# pcb.net
KiCad netlist of a schematic drawn in EasyEDA Pro
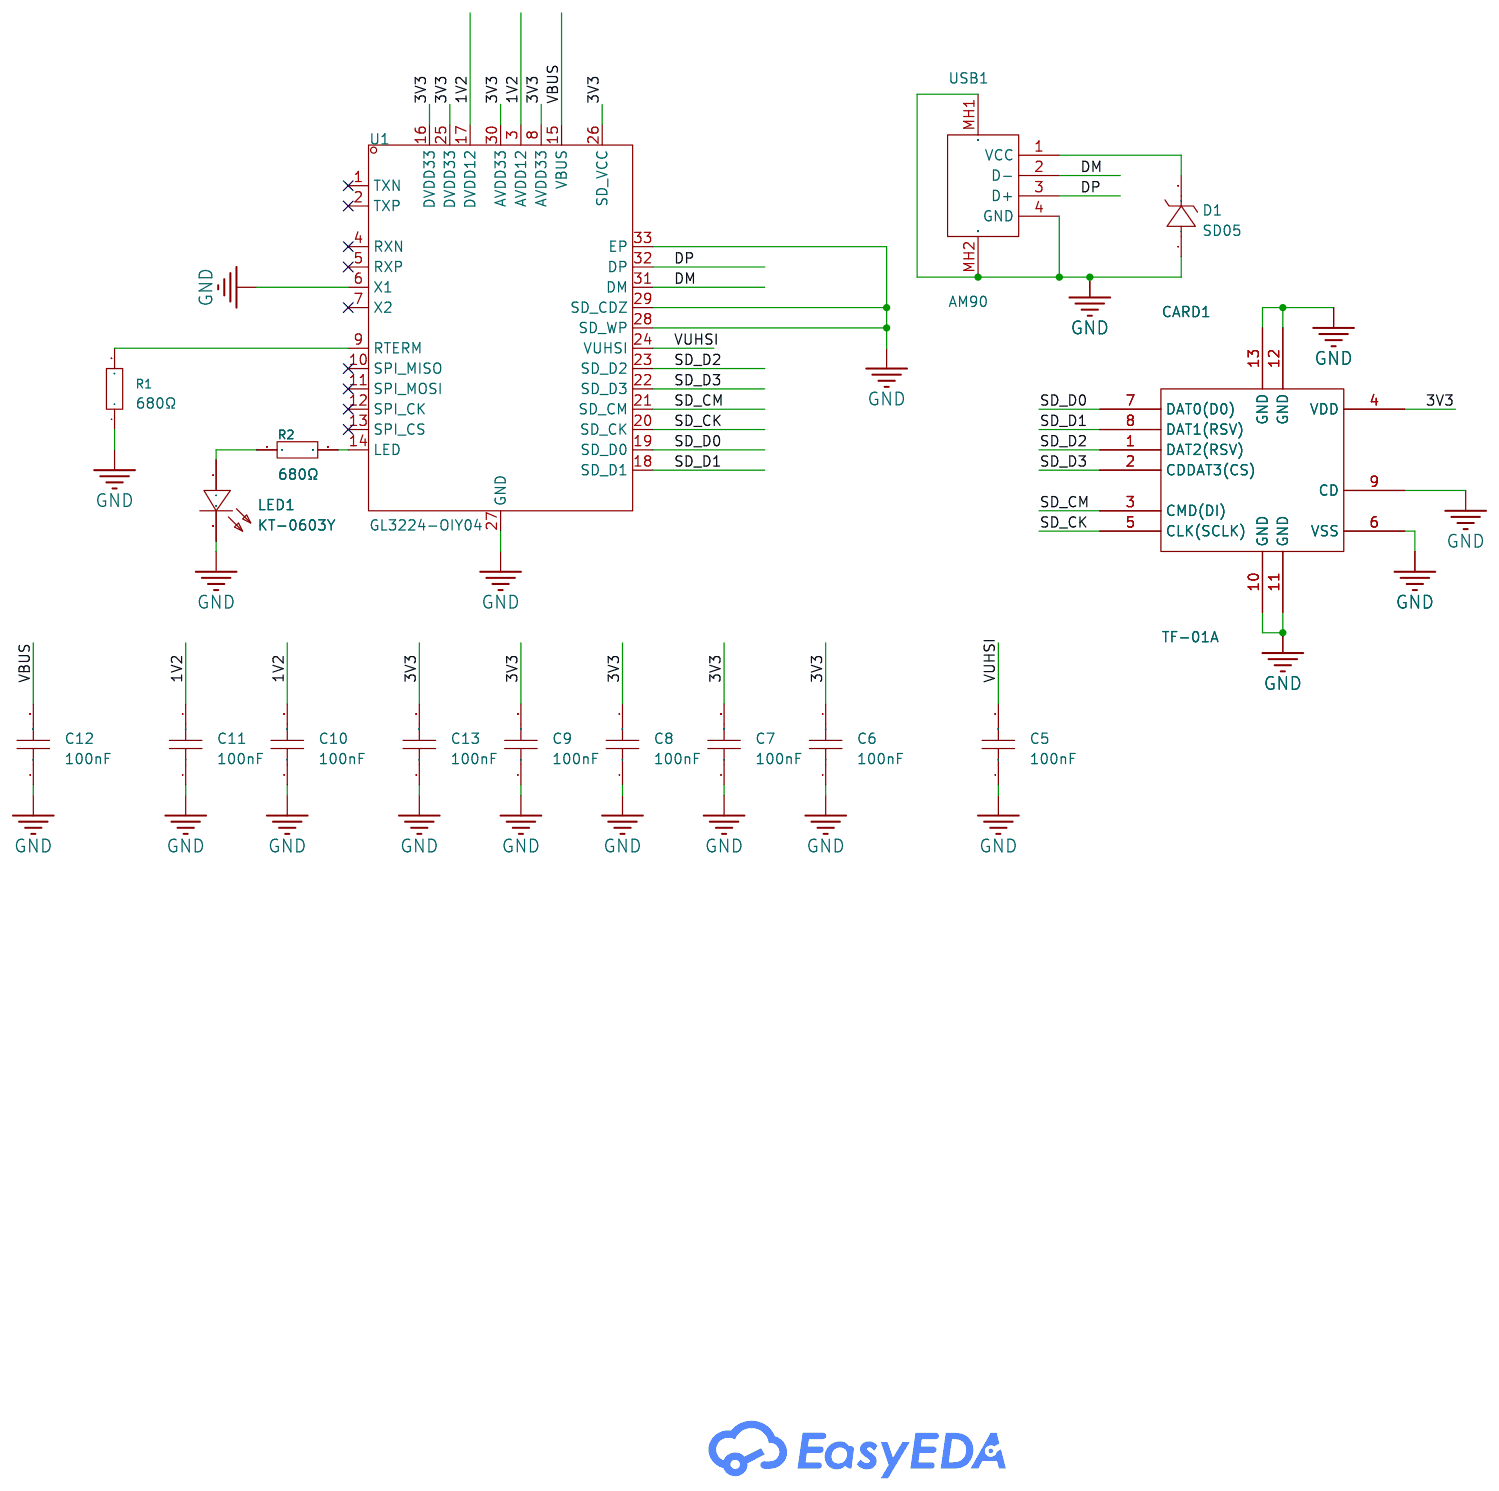
[diagram p0: schematic sheet]

(export (version "E")
  (design (tool "Eeschema 10.0.6"))
  (components
    (comp (ref "C5")
      (value "100nF")
      (footprint "easyedapro:C0402")
      (description "Capacitance:100nF Tolerance:±10% Tolerance:±10% Voltage Rating:16V Temperature Coefficient:X7R")
      (fields
        (field (name "Manufacturer Part") "CL05B104KO5NNNC")
        (field (name "Manufacturer") "SAMSUNG(三星)")
      )
      (libsource (lib "easyedapro") (part "CL05B104KO5NNNC"))
    )
    (comp (ref "C6")
      (value "100nF")
      (footprint "easyedapro:C0402")
      (description "Capacitance:100nF Tolerance:±10% Tolerance:±10% Voltage Rating:16V Temperature Coefficient:X7R")
      (fields
        (field (name "Manufacturer Part") "CL05B104KO5NNNC")
        (field (name "Manufacturer") "SAMSUNG(三星)")
      )
      (libsource (lib "easyedapro") (part "CL05B104KO5NNNC"))
    )
    (comp (ref "C7")
      (value "100nF")
      (footprint "easyedapro:C0402")
      (description "Capacitance:100nF Tolerance:±10% Tolerance:±10% Voltage Rating:16V Temperature Coefficient:X7R")
      (fields
        (field (name "Manufacturer Part") "CL05B104KO5NNNC")
        (field (name "Manufacturer") "SAMSUNG(三星)")
      )
      (libsource (lib "easyedapro") (part "CL05B104KO5NNNC"))
    )
    (comp (ref "C8")
      (value "100nF")
      (footprint "easyedapro:C0402")
      (description "Capacitance:100nF Tolerance:±10% Tolerance:±10% Voltage Rating:16V Temperature Coefficient:X7R")
      (fields
        (field (name "Manufacturer Part") "CL05B104KO5NNNC")
        (field (name "Manufacturer") "SAMSUNG(三星)")
      )
      (libsource (lib "easyedapro") (part "CL05B104KO5NNNC"))
    )
    (comp (ref "C9")
      (value "100nF")
      (footprint "easyedapro:C0402")
      (description "Capacitance:100nF Tolerance:±10% Tolerance:±10% Voltage Rating:16V Temperature Coefficient:X7R")
      (fields
        (field (name "Manufacturer Part") "CL05B104KO5NNNC")
        (field (name "Manufacturer") "SAMSUNG(三星)")
      )
      (libsource (lib "easyedapro") (part "CL05B104KO5NNNC"))
    )
    (comp (ref "C10")
      (value "100nF")
      (footprint "easyedapro:C0402")
      (description "Capacitance:100nF Tolerance:±10% Tolerance:±10% Voltage Rating:16V Temperature Coefficient:X7R")
      (fields
        (field (name "Manufacturer Part") "CL05B104KO5NNNC")
        (field (name "Manufacturer") "SAMSUNG(三星)")
      )
      (libsource (lib "easyedapro") (part "CL05B104KO5NNNC"))
    )
    (comp (ref "C11")
      (value "100nF")
      (footprint "easyedapro:C0402")
      (description "Capacitance:100nF Tolerance:±10% Tolerance:±10% Voltage Rating:16V Temperature Coefficient:X7R")
      (fields
        (field (name "Manufacturer Part") "CL05B104KO5NNNC")
        (field (name "Manufacturer") "SAMSUNG(三星)")
      )
      (libsource (lib "easyedapro") (part "CL05B104KO5NNNC"))
    )
    (comp (ref "C12")
      (value "100nF")
      (footprint "easyedapro:C0402")
      (description "Capacitance:100nF Tolerance:±10% Tolerance:±10% Voltage Rating:16V Temperature Coefficient:X7R")
      (fields
        (field (name "Manufacturer Part") "CL05B104KO5NNNC")
        (field (name "Manufacturer") "SAMSUNG(三星)")
      )
      (libsource (lib "easyedapro") (part "CL05B104KO5NNNC"))
    )
    (comp (ref "C13")
      (value "100nF")
      (footprint "easyedapro:C0402")
      (description "Capacitance:100nF Tolerance:±10% Tolerance:±10% Voltage Rating:16V Temperature Coefficient:X7R")
      (fields
        (field (name "Manufacturer Part") "CL05B104KO5NNNC")
        (field (name "Manufacturer") "SAMSUNG(三星)")
      )
      (libsource (lib "easyedapro") (part "CL05B104KO5NNNC"))
    )
    (comp (ref "CARD1")
      (value "TF-01A")
      (footprint "easyedapro:TF-SMD_TF-01A")
      (fields (field (name "Manufacturer") "韩国韩荣"))
      (libsource (lib "easyedapro") (part "TF-01A"))
    )
    (comp (ref "D1")
      (value "SD05")
      (footprint "easyedapro:SOD-323_L1.8-W1.3-LS2.5-FD")
      (fields (field (name "Manufacturer") "MDD(辰达半导体)"))
      (libsource (lib "easyedapro") (part "SD05_C502527"))
    )
    (comp (ref "LED1")
      (value "KT-0603Y")
      (footprint "easyedapro:LED0603-R-RD")
      (fields (field (name "Manufacturer") "KENTO"))
      (libsource (lib "easyedapro") (part "0603YYellow light 90-110"))
    )
    (comp (ref "R1")
      (value "680Ω")
      (footprint "easyedapro:R0603")
      (fields
        (field (name "Manufacturer Part") "0603WAF6800T5E")
        (field (name "Manufacturer") "UNI-ROYAL(厚声)")
      )
      (libsource (lib "easyedapro") (part "0603WAF6800T5E"))
    )
    (comp (ref "R2")
      (value "680Ω")
      (footprint "easyedapro:R0603")
      (fields
        (field (name "Manufacturer Part") "0603WAF6800T5E")
        (field (name "Manufacturer") "UNI-ROYAL(厚声)")
      )
      (libsource (lib "easyedapro") (part "0603WAF6800T5E"))
    )
    (comp (ref "U1")
      (value "GL3224-OIY04")
      (footprint "easyedapro:HQFN-32_L5.0-W5.0-P0.50-BL-EP3.0")
      (fields (field (name "Manufacturer") "GENESYS(创惟)"))
      (libsource (lib "easyedapro") (part "GL3224-OIY04"))
    )
    (comp (ref "USB1")
      (value "AM90")
      (footprint "easyedapro:USB-AM-TH_AM90")
      (fields (field (name "Manufacturer") "SHOU HAN(首韩)"))
      (libsource (lib "easyedapro") (part "AM90"))
    )
  )
  (nets
    (net (code "1") (name "/1V2") (class "Default")
      (node (ref "C10") (pin "2") (pinfunction "2_2") (pintype "unspecified"))
      (node (ref "C11") (pin "2") (pinfunction "2_2") (pintype "unspecified"))
      (node (ref "U1") (pin "17") (pinfunction "DVDD12_17") (pintype "unspecified"))
      (node (ref "U1") (pin "3") (pinfunction "AVDD12_3") (pintype "unspecified"))
    )
    (net (code "2") (name "/3V3") (class "Default")
      (node (ref "C13") (pin "2") (pinfunction "2_2") (pintype "unspecified"))
      (node (ref "C6") (pin "2") (pinfunction "2_2") (pintype "unspecified"))
      (node (ref "C7") (pin "2") (pinfunction "2_2") (pintype "unspecified"))
      (node (ref "C8") (pin "2") (pinfunction "2_2") (pintype "unspecified"))
      (node (ref "C9") (pin "2") (pinfunction "2_2") (pintype "unspecified"))
      (node (ref "CARD1") (pin "4") (pinfunction "VDD_4") (pintype "input"))
      (node (ref "U1") (pin "16") (pinfunction "DVDD33_16") (pintype "unspecified"))
      (node (ref "U1") (pin "25") (pinfunction "DVDD33_25") (pintype "unspecified"))
      (node (ref "U1") (pin "26") (pinfunction "SD_VCC_26") (pintype "unspecified"))
      (node (ref "U1") (pin "30") (pinfunction "AVDD33_30") (pintype "unspecified"))
      (node (ref "U1") (pin "8") (pinfunction "AVDD33_8") (pintype "unspecified"))
    )
    (net (code "3") (name "/DM") (class "Default")
      (node (ref "U1") (pin "31") (pinfunction "DM_31") (pintype "unspecified"))
      (node (ref "USB1") (pin "2") (pinfunction "D-_2") (pintype "input"))
    )
    (net (code "4") (name "/DP") (class "Default")
      (node (ref "U1") (pin "32") (pinfunction "DP_32") (pintype "unspecified"))
      (node (ref "USB1") (pin "3") (pinfunction "D+_3") (pintype "input"))
    )
    (net (code "5") (name "/SD_CK") (class "Default")
      (node (ref "CARD1") (pin "5") (pinfunction "CLK(SCLK)_5") (pintype "input"))
      (node (ref "U1") (pin "20") (pinfunction "SD_CK_20") (pintype "unspecified"))
    )
    (net (code "6") (name "/SD_CM") (class "Default")
      (node (ref "CARD1") (pin "3") (pinfunction "CMD(DI)_3") (pintype "input"))
      (node (ref "U1") (pin "21") (pinfunction "SD_CM_21") (pintype "unspecified"))
    )
    (net (code "7") (name "/SD_D0") (class "Default")
      (node (ref "CARD1") (pin "7") (pinfunction "DAT0(D0)_7") (pintype "bidirectional"))
      (node (ref "U1") (pin "19") (pinfunction "SD_D0_19") (pintype "unspecified"))
    )
    (net (code "8") (name "/SD_D1") (class "Default")
      (node (ref "CARD1") (pin "8") (pinfunction "DAT1(RSV)_8") (pintype "bidirectional"))
      (node (ref "U1") (pin "18") (pinfunction "SD_D1_18") (pintype "unspecified"))
    )
    (net (code "9") (name "/SD_D2") (class "Default")
      (node (ref "CARD1") (pin "1") (pinfunction "DAT2(RSV)_1") (pintype "bidirectional"))
      (node (ref "U1") (pin "23") (pinfunction "SD_D2_23") (pintype "unspecified"))
    )
    (net (code "10") (name "/SD_D3") (class "Default")
      (node (ref "CARD1") (pin "2") (pinfunction "CDDAT3(CS)_2") (pintype "bidirectional"))
      (node (ref "U1") (pin "22") (pinfunction "SD_D3_22") (pintype "unspecified"))
    )
    (net (code "11") (name "/VBUS") (class "Default")
      (node (ref "C12") (pin "2") (pinfunction "2_2") (pintype "unspecified"))
      (node (ref "U1") (pin "15") (pinfunction "VBUS_15") (pintype "unspecified"))
    )
    (net (code "12") (name "/VUHSI") (class "Default")
      (node (ref "C5") (pin "2") (pinfunction "2_2") (pintype "unspecified"))
      (node (ref "U1") (pin "24") (pinfunction "VUHSI_24") (pintype "unspecified"))
    )
    (net (code "13") (name "GND") (class "Default")
      (node (ref "C10") (pin "1") (pinfunction "1_1") (pintype "unspecified"))
      (node (ref "C11") (pin "1") (pinfunction "1_1") (pintype "unspecified"))
      (node (ref "C12") (pin "1") (pinfunction "1_1") (pintype "unspecified"))
      (node (ref "C13") (pin "1") (pinfunction "1_1") (pintype "unspecified"))
      (node (ref "C5") (pin "1") (pinfunction "1_1") (pintype "unspecified"))
      (node (ref "C6") (pin "1") (pinfunction "1_1") (pintype "unspecified"))
      (node (ref "C7") (pin "1") (pinfunction "1_1") (pintype "unspecified"))
      (node (ref "C8") (pin "1") (pinfunction "1_1") (pintype "unspecified"))
      (node (ref "C9") (pin "1") (pinfunction "1_1") (pintype "unspecified"))
      (node (ref "CARD1") (pin "10") (pinfunction "GND_10") (pintype "input"))
      (node (ref "CARD1") (pin "11") (pinfunction "GND_11") (pintype "input"))
      (node (ref "CARD1") (pin "12") (pinfunction "GND_12") (pintype "input"))
      (node (ref "CARD1") (pin "13") (pinfunction "GND_13") (pintype "input"))
      (node (ref "CARD1") (pin "6") (pinfunction "VSS_6") (pintype "input"))
      (node (ref "CARD1") (pin "9") (pinfunction "CD_9") (pintype "input"))
      (node (ref "D1") (pin "1") (pinfunction "A_1") (pintype "unspecified"))
      (node (ref "LED1") (pin "2") (pinfunction "K_2") (pintype "unspecified"))
      (node (ref "R1") (pin "1") (pinfunction "1_1") (pintype "input"))
      (node (ref "U1") (pin "27") (pinfunction "GND_27") (pintype "unspecified"))
      (node (ref "U1") (pin "28") (pinfunction "SD_WP_28") (pintype "unspecified"))
      (node (ref "U1") (pin "29") (pinfunction "SD_CDZ_29") (pintype "unspecified"))
      (node (ref "U1") (pin "33") (pinfunction "EP_33") (pintype "unspecified"))
      (node (ref "U1") (pin "6") (pinfunction "X1_6") (pintype "unspecified"))
      (node (ref "USB1") (pin "4") (pinfunction "GND_4") (pintype "input"))
      (node (ref "USB1") (pin "MH1") (pinfunction "MH1_MH1") (pintype "unspecified"))
      (node (ref "USB1") (pin "MH2") (pinfunction "MH2_MH2") (pintype "unspecified"))
    )
    (net (code "14") (name "Net-(D1-K)") (class "Default")
      (node (ref "D1") (pin "2") (pinfunction "K_2") (pintype "unspecified"))
      (node (ref "USB1") (pin "1") (pinfunction "VCC_1") (pintype "input"))
    )
    (net (code "15") (name "Net-(LED1-A)") (class "Default")
      (node (ref "LED1") (pin "1") (pinfunction "A_1") (pintype "unspecified"))
      (node (ref "R2") (pin "1") (pinfunction "1_1") (pintype "input"))
    )
    (net (code "16") (name "Net-(U1-LED)") (class "Default")
      (node (ref "R2") (pin "2") (pinfunction "2_2") (pintype "input"))
      (node (ref "U1") (pin "14") (pinfunction "LED_14") (pintype "unspecified"))
    )
    (net (code "17") (name "Net-(U1-RTERM)") (class "Default")
      (node (ref "R1") (pin "2") (pinfunction "2_2") (pintype "input"))
      (node (ref "U1") (pin "9") (pinfunction "RTERM_9") (pintype "unspecified"))
    )
    (net (code "18") (name "unconnected-(U1-RXN-Pad4)") (class "Default")
      (node (ref "U1") (pin "4") (pinfunction "RXN_4") (pintype "unspecified+no_connect"))
    )
    (net (code "19") (name "unconnected-(U1-RXP-Pad5)") (class "Default")
      (node (ref "U1") (pin "5") (pinfunction "RXP_5") (pintype "unspecified+no_connect"))
    )
    (net (code "20") (name "unconnected-(U1-SPI_CK-Pad12)") (class "Default")
      (node (ref "U1") (pin "12") (pinfunction "SPI_CK_12") (pintype "unspecified+no_connect"))
    )
    (net (code "21") (name "unconnected-(U1-SPI_CS-Pad13)") (class "Default")
      (node (ref "U1") (pin "13") (pinfunction "SPI_CS_13") (pintype "unspecified+no_connect"))
    )
    (net (code "22") (name "unconnected-(U1-SPI_MISO-Pad10)") (class "Default")
      (node (ref "U1") (pin "10") (pinfunction "SPI_MISO_10") (pintype "unspecified+no_connect"))
    )
    (net (code "23") (name "unconnected-(U1-SPI_MOSI-Pad11)") (class "Default")
      (node (ref "U1") (pin "11") (pinfunction "SPI_MOSI_11") (pintype "unspecified+no_connect"))
    )
    (net (code "24") (name "unconnected-(U1-TXN-Pad1)") (class "Default")
      (node (ref "U1") (pin "1") (pinfunction "TXN_1") (pintype "unspecified+no_connect"))
    )
    (net (code "25") (name "unconnected-(U1-TXP-Pad2)") (class "Default")
      (node (ref "U1") (pin "2") (pinfunction "TXP_2") (pintype "unspecified+no_connect"))
    )
    (net (code "26") (name "unconnected-(U1-X2-Pad7)") (class "Default")
      (node (ref "U1") (pin "7") (pinfunction "X2_7") (pintype "unspecified+no_connect"))
    )
  )
)
